# breakout2_1.net
KiCad netlist of a schematic drawn in EAGLE
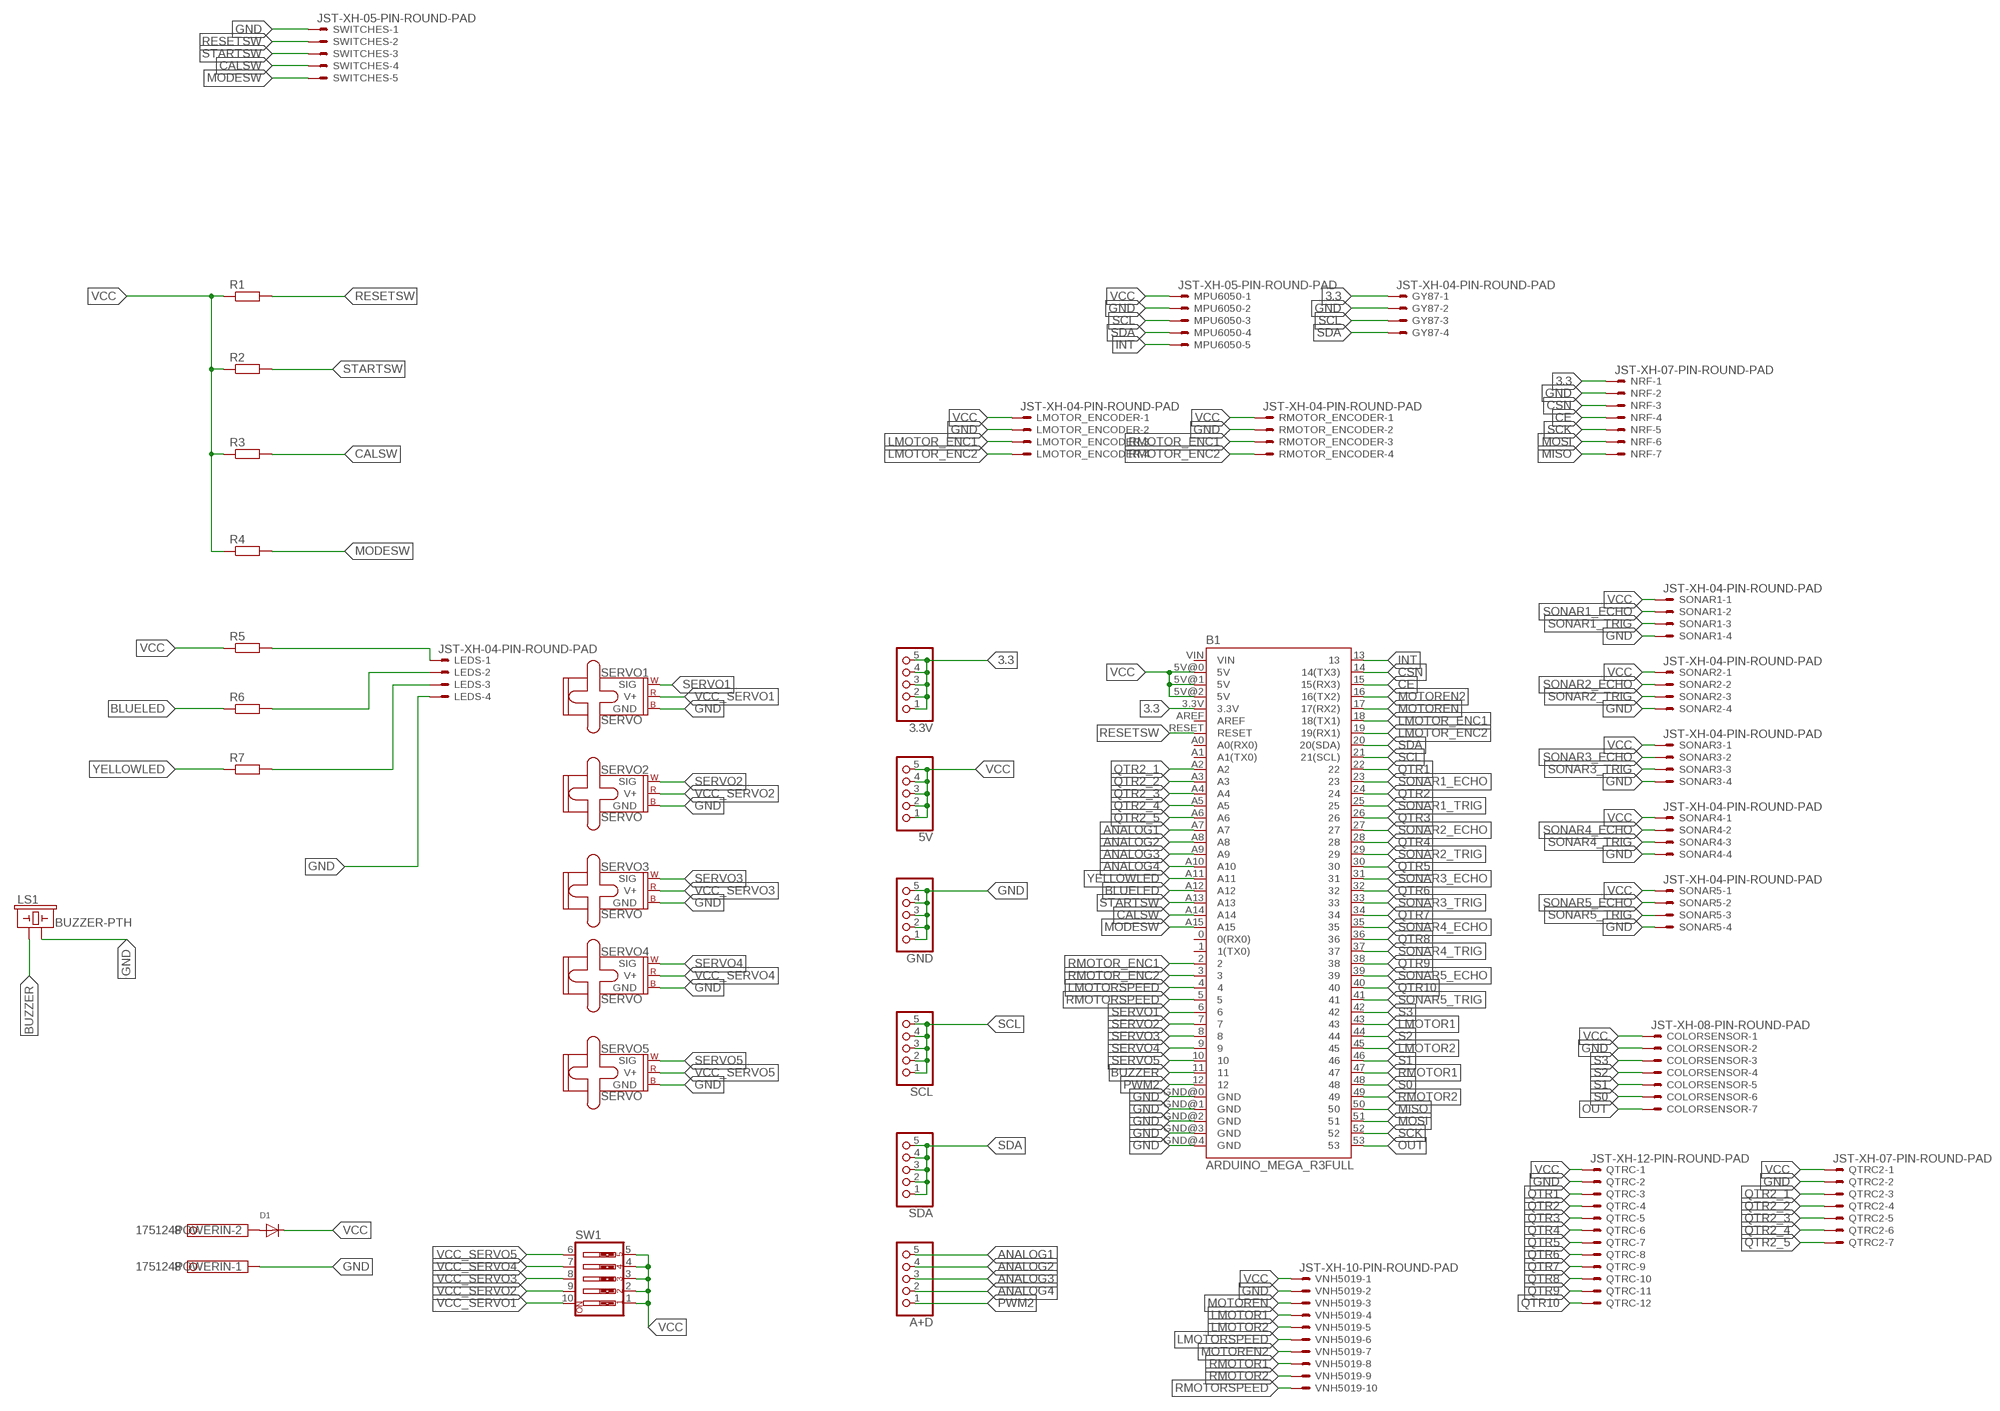
[diagram p0: schematic, sheet 1]

(export (version "E")
  (design (tool "Eeschema 10.0.6"))
  (components
    (comp (ref "3.3V")
      (value "PINHD-1X55X2MM")
      (footprint "eagle-import:1_05X2MM")
      (libsource (lib "eagle-import") (part "PINHD-1X55X2MM"))
    )
    (comp (ref "5V")
      (value "PINHD-1X55X2MM")
      (footprint "eagle-import:1_05X2MM")
      (libsource (lib "eagle-import") (part "PINHD-1X55X2MM"))
    )
    (comp (ref "A+D")
      (value "PINHD-1X55X2MM")
      (footprint "eagle-import:1_05X2MM")
      (libsource (lib "eagle-import") (part "PINHD-1X55X2MM"))
    )
    (comp (ref "B1")
      (value "ARDUINO_MEGA_R3FULL")
      (footprint "eagle-import:ARDUINO_MEGA")
      (libsource (lib "eagle-import") (part "ARDUINO_MEGA_R3FULL"))
    )
    (comp (ref "COLORSENSOR")
      (value "JST-XH-08-PIN-ROUND-PAD")
      (footprint "eagle-import:JST-XH-08-PACKAGE-ROUND-PAD")
      (libsource (lib "eagle-import") (part "JST-XH-08-PIN-ROUND-PAD"))
    )
    (comp (ref "D1")
      (value "DIODEDO-1N4148")
      (footprint "eagle-import:DO-1N4148")
      (libsource (lib "eagle-import") (part "DIODEDO-1N4148"))
    )
    (comp (ref "GND")
      (value "PINHD-1X55X2MM")
      (footprint "eagle-import:1_05X2MM")
      (libsource (lib "eagle-import") (part "PINHD-1X55X2MM"))
    )
    (comp (ref "GY87")
      (value "JST-XH-04-PIN-ROUND-PAD")
      (footprint "eagle-import:JST-XH-04-PACKAGE-ROUND-PAD")
      (libsource (lib "eagle-import") (part "JST-XH-04-PIN-ROUND-PAD"))
    )
    (comp (ref "LEDS")
      (value "JST-XH-04-PIN-ROUND-PAD")
      (footprint "eagle-import:JST-XH-04-PACKAGE-ROUND-PAD")
      (libsource (lib "eagle-import") (part "JST-XH-04-PIN-ROUND-PAD"))
    )
    (comp (ref "LMOTOR_ENCODER")
      (value "JST-XH-04-PIN-ROUND-PAD")
      (footprint "eagle-import:JST-XH-04-PACKAGE-ROUND-PAD")
      (libsource (lib "eagle-import") (part "JST-XH-04-PIN-ROUND-PAD"))
    )
    (comp (ref "LS1")
      (value "BUZZER-PTH")
      (footprint "eagle-import:BUZZER-12MM")
      (libsource (lib "eagle-import") (part "BUZZER-PTH"))
    )
    (comp (ref "MPU6050")
      (value "JST-XH-05-PIN-ROUND-PAD")
      (footprint "eagle-import:JST-XH-05-PACKAGE-ROUND-PAD")
      (libsource (lib "eagle-import") (part "JST-XH-05-PIN-ROUND-PAD"))
    )
    (comp (ref "NRF")
      (value "JST-XH-07-PIN-ROUND-PAD")
      (footprint "eagle-import:JST-XH-07-PACKAGE-ROUND-PAD")
      (libsource (lib "eagle-import") (part "JST-XH-07-PIN-ROUND-PAD"))
    )
    (comp (ref "POWERIN")
      (value "1751248")
      (footprint "eagle-import:1751248")
      (libsource (lib "eagle-import") (part "1751248"))
    )
    (comp (ref "QTRC")
      (value "JST-XH-12-PIN-ROUND-PAD")
      (footprint "eagle-import:JST-XH-12-PACKAGE-ROUND-PAD")
      (libsource (lib "eagle-import") (part "JST-XH-12-PIN-ROUND-PAD"))
    )
    (comp (ref "QTRC2")
      (value "JST-XH-07-PIN-ROUND-PAD")
      (footprint "eagle-import:JST-XH-07-PACKAGE-ROUND-PAD")
      (libsource (lib "eagle-import") (part "JST-XH-07-PIN-ROUND-PAD"))
    )
    (comp (ref "R1")
      (value "R-EU_0204/7")
      (footprint "eagle-import:0204_7")
      (libsource (lib "eagle-import") (part "R-EU_0204/7"))
    )
    (comp (ref "R2")
      (value "R-EU_0204/7")
      (footprint "eagle-import:0204_7")
      (libsource (lib "eagle-import") (part "R-EU_0204/7"))
    )
    (comp (ref "R3")
      (value "R-EU_0204/7")
      (footprint "eagle-import:0204_7")
      (libsource (lib "eagle-import") (part "R-EU_0204/7"))
    )
    (comp (ref "R4")
      (value "R-EU_0204/7")
      (footprint "eagle-import:0204_7")
      (libsource (lib "eagle-import") (part "R-EU_0204/7"))
    )
    (comp (ref "R5")
      (value "R-EU_0204/7")
      (footprint "eagle-import:0204_7")
      (libsource (lib "eagle-import") (part "R-EU_0204/7"))
    )
    (comp (ref "R6")
      (value "R-EU_0204/7")
      (footprint "eagle-import:0204_7")
      (libsource (lib "eagle-import") (part "R-EU_0204/7"))
    )
    (comp (ref "R7")
      (value "R-EU_0204/7")
      (footprint "eagle-import:0204_7")
      (libsource (lib "eagle-import") (part "R-EU_0204/7"))
    )
    (comp (ref "RMOTOR_ENCODER")
      (value "JST-XH-04-PIN-ROUND-PAD")
      (footprint "eagle-import:JST-XH-04-PACKAGE-ROUND-PAD")
      (libsource (lib "eagle-import") (part "JST-XH-04-PIN-ROUND-PAD"))
    )
    (comp (ref "SCL")
      (value "PINHD-1X55X2MM")
      (footprint "eagle-import:1_05X2MM")
      (libsource (lib "eagle-import") (part "PINHD-1X55X2MM"))
    )
    (comp (ref "SDA")
      (value "PINHD-1X55X2MM")
      (footprint "eagle-import:1_05X2MM")
      (libsource (lib "eagle-import") (part "PINHD-1X55X2MM"))
    )
    (comp (ref "SERVO1")
      (value "SERVO")
      (footprint "eagle-import:1X03")
      (libsource (lib "eagle-import") (part "SERVO"))
    )
    (comp (ref "SERVO2")
      (value "SERVO")
      (footprint "eagle-import:1X03")
      (libsource (lib "eagle-import") (part "SERVO"))
    )
    (comp (ref "SERVO3")
      (value "SERVO")
      (footprint "eagle-import:1X03")
      (libsource (lib "eagle-import") (part "SERVO"))
    )
    (comp (ref "SERVO4")
      (value "SERVO")
      (footprint "eagle-import:1X03")
      (libsource (lib "eagle-import") (part "SERVO"))
    )
    (comp (ref "SERVO5")
      (value "SERVO")
      (footprint "eagle-import:1X03")
      (libsource (lib "eagle-import") (part "SERVO"))
    )
    (comp (ref "SONAR1")
      (value "JST-XH-04-PIN-ROUND-PAD")
      (footprint "eagle-import:JST-XH-04-PACKAGE-ROUND-PAD")
      (libsource (lib "eagle-import") (part "JST-XH-04-PIN-ROUND-PAD"))
    )
    (comp (ref "SONAR2")
      (value "JST-XH-04-PIN-ROUND-PAD")
      (footprint "eagle-import:JST-XH-04-PACKAGE-ROUND-PAD")
      (libsource (lib "eagle-import") (part "JST-XH-04-PIN-ROUND-PAD"))
    )
    (comp (ref "SONAR3")
      (value "JST-XH-04-PIN-ROUND-PAD")
      (footprint "eagle-import:JST-XH-04-PACKAGE-ROUND-PAD")
      (libsource (lib "eagle-import") (part "JST-XH-04-PIN-ROUND-PAD"))
    )
    (comp (ref "SONAR4")
      (value "JST-XH-04-PIN-ROUND-PAD")
      (footprint "eagle-import:JST-XH-04-PACKAGE-ROUND-PAD")
      (libsource (lib "eagle-import") (part "JST-XH-04-PIN-ROUND-PAD"))
    )
    (comp (ref "SONAR5")
      (value "JST-XH-04-PIN-ROUND-PAD")
      (footprint "eagle-import:JST-XH-04-PACKAGE-ROUND-PAD")
      (libsource (lib "eagle-import") (part "JST-XH-04-PIN-ROUND-PAD"))
    )
    (comp (ref "SW1")
      (value "SW_DIP-5")
      (footprint "eagle-import:EDG-05")
      (libsource (lib "eagle-import") (part "SW_DIP-5"))
    )
    (comp (ref "SWITCHES")
      (value "JST-XH-05-PIN-ROUND-PAD")
      (footprint "eagle-import:JST-XH-05-PACKAGE-ROUND-PAD")
      (libsource (lib "eagle-import") (part "JST-XH-05-PIN-ROUND-PAD"))
    )
    (comp (ref "VNH5019")
      (value "JST-XH-10-PIN-ROUND-PAD")
      (footprint "eagle-import:JST-XH-10-PACKAGE-ROUND-PAD")
      (libsource (lib "eagle-import") (part "JST-XH-10-PIN-ROUND-PAD"))
    )
  )
  (nets
    (net (code "1") (name "3.3") (class "Default")
      (node (ref "3.3V") (pin "1") (pinfunction "1_1") (pintype "passive"))
      (node (ref "3.3V") (pin "2") (pinfunction "2_2") (pintype "passive"))
      (node (ref "3.3V") (pin "3") (pinfunction "3_3") (pintype "passive"))
      (node (ref "3.3V") (pin "4") (pinfunction "4_4") (pintype "passive"))
      (node (ref "3.3V") (pin "5") (pinfunction "5_5") (pintype "passive"))
      (node (ref "B1") (pin "3.3V") (pinfunction "3.3V_3.3V") (pintype "bidirectional"))
      (node (ref "GY87") (pin "1") (pinfunction "S_1") (pintype "passive"))
      (node (ref "NRF") (pin "1") (pinfunction "S_1") (pintype "passive"))
    )
    (net (code "2") (name "ANALOG1") (class "Default")
      (node (ref "A+D") (pin "5") (pinfunction "5_5") (pintype "passive"))
      (node (ref "B1") (pin "A7") (pinfunction "A7_A7") (pintype "bidirectional"))
    )
    (net (code "3") (name "ANALOG2") (class "Default")
      (node (ref "A+D") (pin "4") (pinfunction "4_4") (pintype "passive"))
      (node (ref "B1") (pin "A8") (pinfunction "A8_A8") (pintype "bidirectional"))
    )
    (net (code "4") (name "ANALOG3") (class "Default")
      (node (ref "A+D") (pin "3") (pinfunction "3_3") (pintype "passive"))
      (node (ref "B1") (pin "A9") (pinfunction "A9_A9") (pintype "bidirectional"))
    )
    (net (code "5") (name "ANALOG4") (class "Default")
      (node (ref "A+D") (pin "2") (pinfunction "2_2") (pintype "passive"))
      (node (ref "B1") (pin "A10") (pinfunction "A10_A10") (pintype "bidirectional"))
    )
    (net (code "6") (name "BLUELED") (class "Default")
      (node (ref "B1") (pin "A12") (pinfunction "A12_A12") (pintype "bidirectional"))
      (node (ref "R6") (pin "1") (pinfunction "1_1") (pintype "passive"))
    )
    (net (code "7") (name "BUZZER") (class "Default")
      (node (ref "B1") (pin "11") (pinfunction "11_11") (pintype "bidirectional"))
      (node (ref "LS1") (pin "+") (pinfunction "1_+") (pintype "passive"))
    )
    (net (code "8") (name "CALSW") (class "Default")
      (node (ref "B1") (pin "A14") (pinfunction "A14_A14") (pintype "bidirectional"))
      (node (ref "R3") (pin "2") (pinfunction "2_2") (pintype "passive"))
      (node (ref "SWITCHES") (pin "4") (pinfunction "S_4") (pintype "passive"))
    )
    (net (code "9") (name "CE") (class "Default")
      (node (ref "B1") (pin "15") (pinfunction "15(RX3)_15") (pintype "bidirectional"))
      (node (ref "NRF") (pin "4") (pinfunction "S_4") (pintype "passive"))
    )
    (net (code "10") (name "CSN") (class "Default")
      (node (ref "B1") (pin "14") (pinfunction "14(TX3)_14") (pintype "bidirectional"))
      (node (ref "NRF") (pin "3") (pinfunction "S_3") (pintype "passive"))
    )
    (net (code "11") (name "GND") (class "Default")
      (node (ref "B1") (pin "GND@0") (pinfunction "GND_GND@0") (pintype "bidirectional"))
      (node (ref "B1") (pin "GND@1") (pinfunction "GND_GND@1") (pintype "bidirectional"))
      (node (ref "B1") (pin "GND@2") (pinfunction "GND_GND@2") (pintype "bidirectional"))
      (node (ref "B1") (pin "GND@3") (pinfunction "GND_GND@3") (pintype "bidirectional"))
      (node (ref "B1") (pin "GND@4") (pinfunction "GND_GND@4") (pintype "bidirectional"))
      (node (ref "COLORSENSOR") (pin "2") (pinfunction "S_2") (pintype "passive"))
      (node (ref "GND") (pin "1") (pinfunction "1_1") (pintype "passive"))
      (node (ref "GND") (pin "2") (pinfunction "2_2") (pintype "passive"))
      (node (ref "GND") (pin "3") (pinfunction "3_3") (pintype "passive"))
      (node (ref "GND") (pin "4") (pinfunction "4_4") (pintype "passive"))
      (node (ref "GND") (pin "5") (pinfunction "5_5") (pintype "passive"))
      (node (ref "GY87") (pin "2") (pinfunction "S_2") (pintype "passive"))
      (node (ref "LEDS") (pin "4") (pinfunction "S_4") (pintype "passive"))
      (node (ref "LMOTOR_ENCODER") (pin "2") (pinfunction "S_2") (pintype "passive"))
      (node (ref "LS1") (pin "-") (pinfunction "2_-") (pintype "passive"))
      (node (ref "MPU6050") (pin "2") (pinfunction "S_2") (pintype "passive"))
      (node (ref "NRF") (pin "2") (pinfunction "S_2") (pintype "passive"))
      (node (ref "POWERIN") (pin "1") (pinfunction "K_1") (pintype "passive"))
      (node (ref "QTRC") (pin "2") (pinfunction "S_2") (pintype "passive"))
      (node (ref "QTRC2") (pin "2") (pinfunction "S_2") (pintype "passive"))
      (node (ref "RMOTOR_ENCODER") (pin "2") (pinfunction "S_2") (pintype "passive"))
      (node (ref "SERVO1") (pin "3") (pinfunction "GND_3") (pintype "bidirectional"))
      (node (ref "SERVO2") (pin "3") (pinfunction "GND_3") (pintype "bidirectional"))
      (node (ref "SERVO3") (pin "3") (pinfunction "GND_3") (pintype "bidirectional"))
      (node (ref "SERVO4") (pin "3") (pinfunction "GND_3") (pintype "bidirectional"))
      (node (ref "SERVO5") (pin "3") (pinfunction "GND_3") (pintype "bidirectional"))
      (node (ref "SONAR1") (pin "4") (pinfunction "S_4") (pintype "passive"))
      (node (ref "SONAR2") (pin "4") (pinfunction "S_4") (pintype "passive"))
      (node (ref "SONAR3") (pin "4") (pinfunction "S_4") (pintype "passive"))
      (node (ref "SONAR4") (pin "4") (pinfunction "S_4") (pintype "passive"))
      (node (ref "SONAR5") (pin "4") (pinfunction "S_4") (pintype "passive"))
      (node (ref "SWITCHES") (pin "1") (pinfunction "S_1") (pintype "passive"))
      (node (ref "VNH5019") (pin "2") (pinfunction "S_2") (pintype "passive"))
    )
    (net (code "12") (name "INT") (class "Default")
      (node (ref "B1") (pin "13") (pinfunction "13_13") (pintype "bidirectional"))
      (node (ref "MPU6050") (pin "5") (pinfunction "S_5") (pintype "passive"))
    )
    (net (code "13") (name "LMOTOR1") (class "Default")
      (node (ref "B1") (pin "43") (pinfunction "43_43") (pintype "bidirectional"))
      (node (ref "VNH5019") (pin "4") (pinfunction "S_4") (pintype "passive"))
    )
    (net (code "14") (name "LMOTOR2") (class "Default")
      (node (ref "B1") (pin "45") (pinfunction "45_45") (pintype "bidirectional"))
      (node (ref "VNH5019") (pin "5") (pinfunction "S_5") (pintype "passive"))
    )
    (net (code "15") (name "LMOTORSPEED") (class "Default")
      (node (ref "B1") (pin "4") (pinfunction "4_4") (pintype "bidirectional"))
      (node (ref "VNH5019") (pin "6") (pinfunction "S_6") (pintype "passive"))
    )
    (net (code "16") (name "LMOTOR_ENC1") (class "Default")
      (node (ref "B1") (pin "18") (pinfunction "18(TX1)_18") (pintype "bidirectional"))
      (node (ref "LMOTOR_ENCODER") (pin "3") (pinfunction "S_3") (pintype "passive"))
    )
    (net (code "17") (name "LMOTOR_ENC2") (class "Default")
      (node (ref "B1") (pin "19") (pinfunction "19(RX1)_19") (pintype "bidirectional"))
      (node (ref "LMOTOR_ENCODER") (pin "4") (pinfunction "S_4") (pintype "passive"))
    )
    (net (code "18") (name "MISO") (class "Default")
      (node (ref "B1") (pin "50") (pinfunction "50_50") (pintype "bidirectional"))
      (node (ref "NRF") (pin "7") (pinfunction "S_7") (pintype "passive"))
    )
    (net (code "19") (name "MODESW") (class "Default")
      (node (ref "B1") (pin "A15") (pinfunction "A15_A15") (pintype "bidirectional"))
      (node (ref "R4") (pin "2") (pinfunction "2_2") (pintype "passive"))
      (node (ref "SWITCHES") (pin "5") (pinfunction "S_5") (pintype "passive"))
    )
    (net (code "20") (name "MOSI") (class "Default")
      (node (ref "B1") (pin "51") (pinfunction "51_51") (pintype "bidirectional"))
      (node (ref "NRF") (pin "6") (pinfunction "S_6") (pintype "passive"))
    )
    (net (code "21") (name "MOTOREN") (class "Default")
      (node (ref "B1") (pin "17") (pinfunction "17(RX2)_17") (pintype "bidirectional"))
      (node (ref "VNH5019") (pin "3") (pinfunction "S_3") (pintype "passive"))
    )
    (net (code "22") (name "MOTOREN2") (class "Default")
      (node (ref "B1") (pin "16") (pinfunction "16(TX2)_16") (pintype "bidirectional"))
      (node (ref "VNH5019") (pin "7") (pinfunction "S_7") (pintype "passive"))
    )
    (net (code "23") (name "Net-(LEDSA-S)") (class "Default")
      (node (ref "LEDS") (pin "1") (pinfunction "S_1") (pintype "passive"))
      (node (ref "R5") (pin "2") (pinfunction "2_2") (pintype "passive"))
    )
    (net (code "24") (name "Net-(LEDSB-S)") (class "Default")
      (node (ref "LEDS") (pin "2") (pinfunction "S_2") (pintype "passive"))
      (node (ref "R6") (pin "2") (pinfunction "2_2") (pintype "passive"))
    )
    (net (code "25") (name "Net-(LEDSC-S)") (class "Default")
      (node (ref "LEDS") (pin "3") (pinfunction "S_3") (pintype "passive"))
      (node (ref "R7") (pin "2") (pinfunction "2_2") (pintype "passive"))
    )
    (net (code "26") (name "Net-(POWERINB-K)") (class "Default")
      (node (ref "D1") (pin "A") (pinfunction "A_A") (pintype "passive"))
      (node (ref "POWERIN") (pin "2") (pinfunction "K_2") (pintype "passive"))
    )
    (net (code "27") (name "OUT") (class "Default")
      (node (ref "B1") (pin "53") (pinfunction "53_53") (pintype "bidirectional"))
      (node (ref "COLORSENSOR") (pin "7") (pinfunction "S_7") (pintype "passive"))
    )
    (net (code "28") (name "PWM2") (class "Default")
      (node (ref "A+D") (pin "1") (pinfunction "1_1") (pintype "passive"))
      (node (ref "B1") (pin "12") (pinfunction "12_12") (pintype "bidirectional"))
    )
    (net (code "29") (name "QTR1") (class "Default")
      (node (ref "B1") (pin "22") (pinfunction "22_22") (pintype "bidirectional"))
      (node (ref "QTRC") (pin "3") (pinfunction "S_3") (pintype "passive"))
    )
    (net (code "30") (name "QTR2") (class "Default")
      (node (ref "B1") (pin "24") (pinfunction "24_24") (pintype "bidirectional"))
      (node (ref "QTRC") (pin "4") (pinfunction "S_4") (pintype "passive"))
    )
    (net (code "31") (name "QTR2_1") (class "Default")
      (node (ref "B1") (pin "A2") (pinfunction "A2_A2") (pintype "bidirectional"))
      (node (ref "QTRC2") (pin "3") (pinfunction "S_3") (pintype "passive"))
    )
    (net (code "32") (name "QTR2_2") (class "Default")
      (node (ref "B1") (pin "A3") (pinfunction "A3_A3") (pintype "bidirectional"))
      (node (ref "QTRC2") (pin "4") (pinfunction "S_4") (pintype "passive"))
    )
    (net (code "33") (name "QTR2_3") (class "Default")
      (node (ref "B1") (pin "A4") (pinfunction "A4_A4") (pintype "bidirectional"))
      (node (ref "QTRC2") (pin "5") (pinfunction "S_5") (pintype "passive"))
    )
    (net (code "34") (name "QTR2_4") (class "Default")
      (node (ref "B1") (pin "A5") (pinfunction "A5_A5") (pintype "bidirectional"))
      (node (ref "QTRC2") (pin "6") (pinfunction "S_6") (pintype "passive"))
    )
    (net (code "35") (name "QTR2_5") (class "Default")
      (node (ref "B1") (pin "A6") (pinfunction "A6_A6") (pintype "bidirectional"))
      (node (ref "QTRC2") (pin "7") (pinfunction "S_7") (pintype "passive"))
    )
    (net (code "36") (name "QTR3") (class "Default")
      (node (ref "B1") (pin "26") (pinfunction "26_26") (pintype "bidirectional"))
      (node (ref "QTRC") (pin "5") (pinfunction "S_5") (pintype "passive"))
    )
    (net (code "37") (name "QTR4") (class "Default")
      (node (ref "B1") (pin "28") (pinfunction "28_28") (pintype "bidirectional"))
      (node (ref "QTRC") (pin "6") (pinfunction "S_6") (pintype "passive"))
    )
    (net (code "38") (name "QTR5") (class "Default")
      (node (ref "B1") (pin "30") (pinfunction "30_30") (pintype "bidirectional"))
      (node (ref "QTRC") (pin "7") (pinfunction "S_7") (pintype "passive"))
    )
    (net (code "39") (name "QTR6") (class "Default")
      (node (ref "B1") (pin "32") (pinfunction "32_32") (pintype "bidirectional"))
      (node (ref "QTRC") (pin "8") (pinfunction "S_8") (pintype "passive"))
    )
    (net (code "40") (name "QTR7") (class "Default")
      (node (ref "B1") (pin "34") (pinfunction "34_34") (pintype "bidirectional"))
      (node (ref "QTRC") (pin "9") (pinfunction "S_9") (pintype "passive"))
    )
    (net (code "41") (name "QTR8") (class "Default")
      (node (ref "B1") (pin "36") (pinfunction "36_36") (pintype "bidirectional"))
      (node (ref "QTRC") (pin "10") (pinfunction "S_10") (pintype "passive"))
    )
    (net (code "42") (name "QTR9") (class "Default")
      (node (ref "B1") (pin "38") (pinfunction "38_38") (pintype "bidirectional"))
      (node (ref "QTRC") (pin "11") (pinfunction "S_11") (pintype "passive"))
    )
    (net (code "43") (name "QTR10") (class "Default")
      (node (ref "B1") (pin "40") (pinfunction "40_40") (pintype "bidirectional"))
      (node (ref "QTRC") (pin "12") (pinfunction "S_12") (pintype "passive"))
    )
    (net (code "44") (name "RESETSW") (class "Default")
      (node (ref "B1") (pin "RESET") (pinfunction "RESET_RESET") (pintype "bidirectional"))
      (node (ref "R1") (pin "2") (pinfunction "2_2") (pintype "passive"))
      (node (ref "SWITCHES") (pin "2") (pinfunction "S_2") (pintype "passive"))
    )
    (net (code "45") (name "RMOTOR1") (class "Default")
      (node (ref "B1") (pin "47") (pinfunction "47_47") (pintype "bidirectional"))
      (node (ref "VNH5019") (pin "8") (pinfunction "S_8") (pintype "passive"))
    )
    (net (code "46") (name "RMOTOR2") (class "Default")
      (node (ref "B1") (pin "49") (pinfunction "49_49") (pintype "bidirectional"))
      (node (ref "VNH5019") (pin "9") (pinfunction "S_9") (pintype "passive"))
    )
    (net (code "47") (name "RMOTORSPEED") (class "Default")
      (node (ref "B1") (pin "5") (pinfunction "5_5") (pintype "bidirectional"))
      (node (ref "VNH5019") (pin "10") (pinfunction "S_10") (pintype "passive"))
    )
    (net (code "48") (name "RMOTOR_ENC1") (class "Default")
      (node (ref "B1") (pin "2") (pinfunction "2_2") (pintype "bidirectional"))
      (node (ref "RMOTOR_ENCODER") (pin "3") (pinfunction "S_3") (pintype "passive"))
    )
    (net (code "49") (name "RMOTOR_ENC2") (class "Default")
      (node (ref "B1") (pin "3") (pinfunction "3_3") (pintype "bidirectional"))
      (node (ref "RMOTOR_ENCODER") (pin "4") (pinfunction "S_4") (pintype "passive"))
    )
    (net (code "50") (name "S0") (class "Default")
      (node (ref "B1") (pin "48") (pinfunction "48_48") (pintype "bidirectional"))
      (node (ref "COLORSENSOR") (pin "6") (pinfunction "S_6") (pintype "passive"))
    )
    (net (code "51") (name "S1") (class "Default")
      (node (ref "B1") (pin "46") (pinfunction "46_46") (pintype "bidirectional"))
      (node (ref "COLORSENSOR") (pin "5") (pinfunction "S_5") (pintype "passive"))
    )
    (net (code "52") (name "S2") (class "Default")
      (node (ref "B1") (pin "44") (pinfunction "44_44") (pintype "bidirectional"))
      (node (ref "COLORSENSOR") (pin "4") (pinfunction "S_4") (pintype "passive"))
    )
    (net (code "53") (name "S3") (class "Default")
      (node (ref "B1") (pin "42") (pinfunction "42_42") (pintype "bidirectional"))
      (node (ref "COLORSENSOR") (pin "3") (pinfunction "S_3") (pintype "passive"))
    )
    (net (code "54") (name "SCK") (class "Default")
      (node (ref "B1") (pin "52") (pinfunction "52_52") (pintype "bidirectional"))
      (node (ref "NRF") (pin "5") (pinfunction "S_5") (pintype "passive"))
    )
    (net (code "55") (name "SCL") (class "Default")
      (node (ref "B1") (pin "21") (pinfunction "21(SCL)_21") (pintype "bidirectional"))
      (node (ref "GY87") (pin "3") (pinfunction "S_3") (pintype "passive"))
      (node (ref "MPU6050") (pin "3") (pinfunction "S_3") (pintype "passive"))
      (node (ref "SCL") (pin "1") (pinfunction "1_1") (pintype "passive"))
      (node (ref "SCL") (pin "2") (pinfunction "2_2") (pintype "passive"))
      (node (ref "SCL") (pin "3") (pinfunction "3_3") (pintype "passive"))
      (node (ref "SCL") (pin "4") (pinfunction "4_4") (pintype "passive"))
      (node (ref "SCL") (pin "5") (pinfunction "5_5") (pintype "passive"))
    )
    (net (code "56") (name "SDA") (class "Default")
      (node (ref "B1") (pin "20") (pinfunction "20(SDA)_20") (pintype "bidirectional"))
      (node (ref "GY87") (pin "4") (pinfunction "S_4") (pintype "passive"))
      (node (ref "MPU6050") (pin "4") (pinfunction "S_4") (pintype "passive"))
      (node (ref "SDA") (pin "1") (pinfunction "1_1") (pintype "passive"))
      (node (ref "SDA") (pin "2") (pinfunction "2_2") (pintype "passive"))
      (node (ref "SDA") (pin "3") (pinfunction "3_3") (pintype "passive"))
      (node (ref "SDA") (pin "4") (pinfunction "4_4") (pintype "passive"))
      (node (ref "SDA") (pin "5") (pinfunction "5_5") (pintype "passive"))
    )
    (net (code "57") (name "SERVO1") (class "Default")
      (node (ref "B1") (pin "6") (pinfunction "6_6") (pintype "bidirectional"))
      (node (ref "SERVO1") (pin "1") (pinfunction "SIG_1") (pintype "bidirectional"))
    )
    (net (code "58") (name "SERVO2") (class "Default")
      (node (ref "B1") (pin "7") (pinfunction "7_7") (pintype "bidirectional"))
      (node (ref "SERVO2") (pin "1") (pinfunction "SIG_1") (pintype "bidirectional"))
    )
    (net (code "59") (name "SERVO3") (class "Default")
      (node (ref "B1") (pin "8") (pinfunction "8_8") (pintype "bidirectional"))
      (node (ref "SERVO3") (pin "1") (pinfunction "SIG_1") (pintype "bidirectional"))
    )
    (net (code "60") (name "SERVO4") (class "Default")
      (node (ref "B1") (pin "9") (pinfunction "9_9") (pintype "bidirectional"))
      (node (ref "SERVO4") (pin "1") (pinfunction "SIG_1") (pintype "bidirectional"))
    )
    (net (code "61") (name "SERVO5") (class "Default")
      (node (ref "B1") (pin "10") (pinfunction "10_10") (pintype "bidirectional"))
      (node (ref "SERVO5") (pin "1") (pinfunction "SIG_1") (pintype "bidirectional"))
    )
    (net (code "62") (name "SONAR1_ECHO") (class "Default")
      (node (ref "B1") (pin "23") (pinfunction "23_23") (pintype "bidirectional"))
      (node (ref "SONAR1") (pin "2") (pinfunction "S_2") (pintype "passive"))
    )
    (net (code "63") (name "SONAR1_TRIG") (class "Default")
      (node (ref "B1") (pin "25") (pinfunction "25_25") (pintype "bidirectional"))
      (node (ref "SONAR1") (pin "3") (pinfunction "S_3") (pintype "passive"))
    )
    (net (code "64") (name "SONAR2_ECHO") (class "Default")
      (node (ref "B1") (pin "27") (pinfunction "27_27") (pintype "bidirectional"))
      (node (ref "SONAR2") (pin "2") (pinfunction "S_2") (pintype "passive"))
    )
    (net (code "65") (name "SONAR2_TRIG") (class "Default")
      (node (ref "B1") (pin "29") (pinfunction "29_29") (pintype "bidirectional"))
      (node (ref "SONAR2") (pin "3") (pinfunction "S_3") (pintype "passive"))
    )
    (net (code "66") (name "SONAR3_ECHO") (class "Default")
      (node (ref "B1") (pin "31") (pinfunction "31_31") (pintype "bidirectional"))
      (node (ref "SONAR3") (pin "2") (pinfunction "S_2") (pintype "passive"))
    )
    (net (code "67") (name "SONAR3_TRIG") (class "Default")
      (node (ref "B1") (pin "33") (pinfunction "33_33") (pintype "bidirectional"))
      (node (ref "SONAR3") (pin "3") (pinfunction "S_3") (pintype "passive"))
    )
    (net (code "68") (name "SONAR4_ECHO") (class "Default")
      (node (ref "B1") (pin "35") (pinfunction "35_35") (pintype "bidirectional"))
      (node (ref "SONAR4") (pin "2") (pinfunction "S_2") (pintype "passive"))
    )
    (net (code "69") (name "SONAR4_TRIG") (class "Default")
      (node (ref "B1") (pin "37") (pinfunction "37_37") (pintype "bidirectional"))
      (node (ref "SONAR4") (pin "3") (pinfunction "S_3") (pintype "passive"))
    )
    (net (code "70") (name "SONAR5_ECHO") (class "Default")
      (node (ref "B1") (pin "39") (pinfunction "39_39") (pintype "bidirectional"))
      (node (ref "SONAR5") (pin "2") (pinfunction "S_2") (pintype "passive"))
    )
    (net (code "71") (name "SONAR5_TRIG") (class "Default")
      (node (ref "B1") (pin "41") (pinfunction "41_41") (pintype "bidirectional"))
      (node (ref "SONAR5") (pin "3") (pinfunction "S_3") (pintype "passive"))
    )
    (net (code "72") (name "STARTSW") (class "Default")
      (node (ref "B1") (pin "A13") (pinfunction "A13_A13") (pintype "bidirectional"))
      (node (ref "R2") (pin "2") (pinfunction "2_2") (pintype "passive"))
      (node (ref "SWITCHES") (pin "3") (pinfunction "S_3") (pintype "passive"))
    )
    (net (code "73") (name "VCC") (class "Default")
      (node (ref "5V") (pin "1") (pinfunction "1_1") (pintype "passive"))
      (node (ref "5V") (pin "2") (pinfunction "2_2") (pintype "passive"))
      (node (ref "5V") (pin "3") (pinfunction "3_3") (pintype "passive"))
      (node (ref "5V") (pin "4") (pinfunction "4_4") (pintype "passive"))
      (node (ref "5V") (pin "5") (pinfunction "5_5") (pintype "passive"))
      (node (ref "B1") (pin "5V@0") (pinfunction "5V_5V@0") (pintype "bidirectional"))
      (node (ref "B1") (pin "5V@1") (pinfunction "5V_5V@1") (pintype "bidirectional"))
      (node (ref "B1") (pin "5V@2") (pinfunction "5V_5V@2") (pintype "bidirectional"))
      (node (ref "COLORSENSOR") (pin "1") (pinfunction "S_1") (pintype "passive"))
      (node (ref "D1") (pin "C") (pinfunction "C_C") (pintype "passive"))
      (node (ref "LMOTOR_ENCODER") (pin "1") (pinfunction "S_1") (pintype "passive"))
      (node (ref "MPU6050") (pin "1") (pinfunction "S_1") (pintype "passive"))
      (node (ref "QTRC") (pin "1") (pinfunction "S_1") (pintype "passive"))
      (node (ref "QTRC2") (pin "1") (pinfunction "S_1") (pintype "passive"))
      (node (ref "R1") (pin "1") (pinfunction "1_1") (pintype "passive"))
      (node (ref "R2") (pin "1") (pinfunction "1_1") (pintype "passive"))
      (node (ref "R3") (pin "1") (pinfunction "1_1") (pintype "passive"))
      (node (ref "R4") (pin "1") (pinfunction "1_1") (pintype "passive"))
      (node (ref "R5") (pin "1") (pinfunction "1_1") (pintype "passive"))
      (node (ref "RMOTOR_ENCODER") (pin "1") (pinfunction "S_1") (pintype "passive"))
      (node (ref "SONAR1") (pin "1") (pinfunction "S_1") (pintype "passive"))
      (node (ref "SONAR2") (pin "1") (pinfunction "S_1") (pintype "passive"))
      (node (ref "SONAR3") (pin "1") (pinfunction "S_1") (pintype "passive"))
      (node (ref "SONAR4") (pin "1") (pinfunction "S_1") (pintype "passive"))
      (node (ref "SONAR5") (pin "1") (pinfunction "S_1") (pintype "passive"))
      (node (ref "SW1") (pin "1") (pinfunction "1_1") (pintype "passive"))
      (node (ref "SW1") (pin "2") (pinfunction "2_2") (pintype "passive"))
      (node (ref "SW1") (pin "3") (pinfunction "3_3") (pintype "passive"))
      (node (ref "SW1") (pin "4") (pinfunction "4_4") (pintype "passive"))
      (node (ref "SW1") (pin "5") (pinfunction "5_5") (pintype "passive"))
      (node (ref "VNH5019") (pin "1") (pinfunction "S_1") (pintype "passive"))
    )
    (net (code "74") (name "VCC_SERVO1") (class "Default")
      (node (ref "SERVO1") (pin "2") (pinfunction "V+_2") (pintype "bidirectional"))
      (node (ref "SW1") (pin "10") (pinfunction "10_10") (pintype "passive"))
    )
    (net (code "75") (name "VCC_SERVO2") (class "Default")
      (node (ref "SERVO2") (pin "2") (pinfunction "V+_2") (pintype "bidirectional"))
      (node (ref "SW1") (pin "9") (pinfunction "9_9") (pintype "passive"))
    )
    (net (code "76") (name "VCC_SERVO3") (class "Default")
      (node (ref "SERVO3") (pin "2") (pinfunction "V+_2") (pintype "bidirectional"))
      (node (ref "SW1") (pin "8") (pinfunction "8_8") (pintype "passive"))
    )
    (net (code "77") (name "VCC_SERVO4") (class "Default")
      (node (ref "SERVO4") (pin "2") (pinfunction "V+_2") (pintype "bidirectional"))
      (node (ref "SW1") (pin "7") (pinfunction "7_7") (pintype "passive"))
    )
    (net (code "78") (name "VCC_SERVO5") (class "Default")
      (node (ref "SERVO5") (pin "2") (pinfunction "V+_2") (pintype "bidirectional"))
      (node (ref "SW1") (pin "6") (pinfunction "6_6") (pintype "passive"))
    )
    (net (code "79") (name "YELLOWLED") (class "Default")
      (node (ref "B1") (pin "A11") (pinfunction "A11_A11") (pintype "bidirectional"))
      (node (ref "R7") (pin "1") (pinfunction "1_1") (pintype "passive"))
    )
    (net (code "80") (name "unconnected-(B1-0(RX0)-Pad0)") (class "Default")
      (node (ref "B1") (pin "0") (pinfunction "0(RX0)_0") (pintype "bidirectional"))
    )
    (net (code "81") (name "unconnected-(B1-1(TX0)-Pad1)") (class "Default")
      (node (ref "B1") (pin "1") (pinfunction "1(TX0)_1") (pintype "bidirectional"))
    )
    (net (code "82") (name "unconnected-(B1-A0(RX0)-PadA0)") (class "Default")
      (node (ref "B1") (pin "A0") (pinfunction "A0(RX0)_A0") (pintype "bidirectional"))
    )
    (net (code "83") (name "unconnected-(B1-A1(TX0)-PadA1)") (class "Default")
      (node (ref "B1") (pin "A1") (pinfunction "A1(TX0)_A1") (pintype "bidirectional"))
    )
    (net (code "84") (name "unconnected-(B1-PadAREF)") (class "Default")
      (node (ref "B1") (pin "AREF") (pinfunction "AREF_AREF") (pintype "bidirectional"))
    )
    (net (code "85") (name "unconnected-(B1-PadVIN)") (class "Default")
      (node (ref "B1") (pin "VIN") (pinfunction "VIN_VIN") (pintype "bidirectional"))
    )
  )
)
